# nrflpc.net
KiCad netlist of a schematic drawn in EAGLE
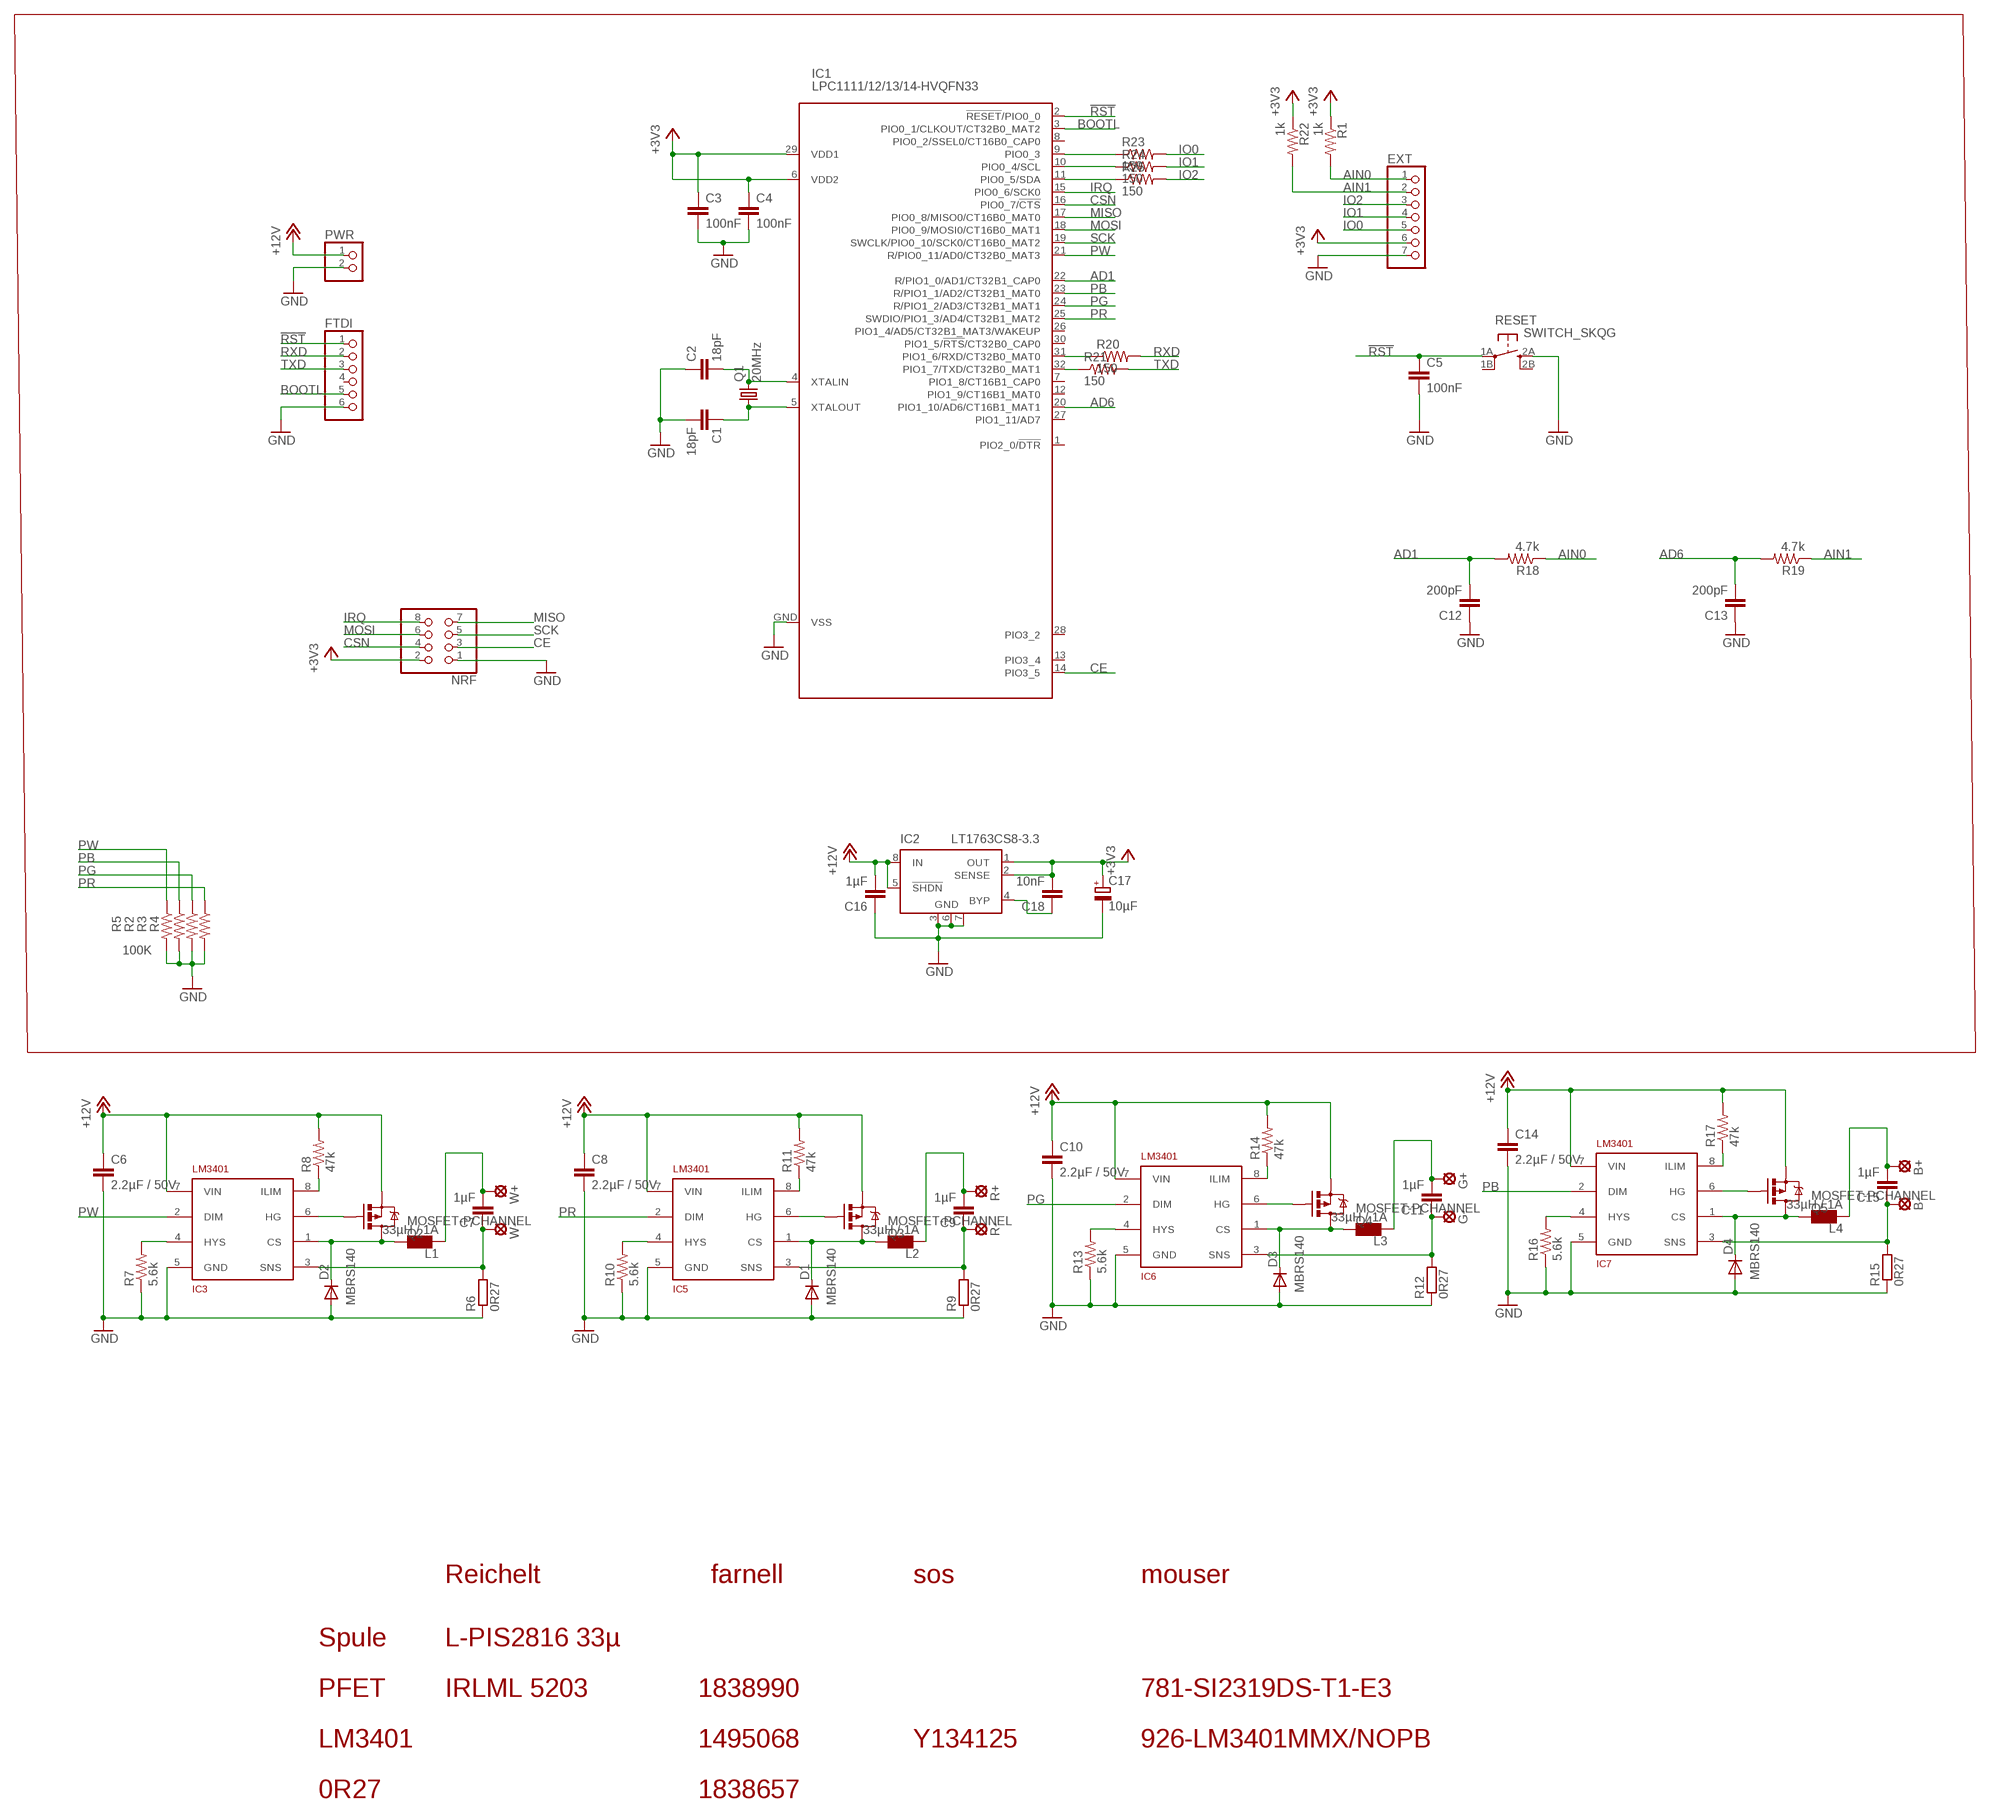
[diagram p0: schematic, sheet 1]

(export (version "E")
  (design (tool "Eeschema 10.0.6"))
  (components
    (comp (ref "B+")
      (value "SE14")
      (footprint "eagle-import:SE14")
      (libsource (lib "eagle-import") (part "SE14"))
    )
    (comp (ref "B-")
      (value "SE14")
      (footprint "eagle-import:SE14")
      (libsource (lib "eagle-import") (part "SE14"))
    )
    (comp (ref "C1")
      (value "18pF")
      (footprint "eagle-import:0402-CAP")
      (libsource (lib "eagle-import") (part "SparkFun-Passives_CAP0402-CAP"))
    )
    (comp (ref "C2")
      (value "18pF")
      (footprint "eagle-import:0402-CAP")
      (libsource (lib "eagle-import") (part "SparkFun-Passives_CAP0402-CAP"))
    )
    (comp (ref "C3")
      (value "100nF")
      (footprint "eagle-import:0402-CAP")
      (libsource (lib "eagle-import") (part "SparkFun-Passives_CAP0402-CAP"))
    )
    (comp (ref "C4")
      (value "100nF")
      (footprint "eagle-import:0402-CAP")
      (libsource (lib "eagle-import") (part "SparkFun-Passives_CAP0402-CAP"))
    )
    (comp (ref "C5")
      (value "100nF")
      (footprint "eagle-import:0402-CAP")
      (libsource (lib "eagle-import") (part "SparkFun-Passives_CAP0402-CAP"))
    )
    (comp (ref "C6")
      (value "2.2µF / 50V")
      (footprint "eagle-import:C1210")
      (libsource (lib "eagle-import") (part "C-EUC1210"))
    )
    (comp (ref "C7")
      (value "1µF")
      (footprint "eagle-import:0805")
      (libsource (lib "eagle-import") (part "CAP0805"))
    )
    (comp (ref "C8")
      (value "2.2µF / 50V")
      (footprint "eagle-import:C1210")
      (libsource (lib "eagle-import") (part "C-EUC1210"))
    )
    (comp (ref "C9")
      (value "1µF")
      (footprint "eagle-import:0805")
      (libsource (lib "eagle-import") (part "CAP0805"))
    )
    (comp (ref "C10")
      (value "2.2µF / 50V")
      (footprint "eagle-import:C1210")
      (libsource (lib "eagle-import") (part "C-EUC1210"))
    )
    (comp (ref "C11")
      (value "1µF")
      (footprint "eagle-import:0805")
      (libsource (lib "eagle-import") (part "CAP0805"))
    )
    (comp (ref "C12")
      (value "200pF")
      (footprint "eagle-import:0402-CAP")
      (libsource (lib "eagle-import") (part "SparkFun-Passives_CAP0402-CAP"))
    )
    (comp (ref "C13")
      (value "200pF")
      (footprint "eagle-import:0402-CAP")
      (libsource (lib "eagle-import") (part "SparkFun-Passives_CAP0402-CAP"))
    )
    (comp (ref "C14")
      (value "2.2µF / 50V")
      (footprint "eagle-import:C1210")
      (libsource (lib "eagle-import") (part "C-EUC1210"))
    )
    (comp (ref "C15")
      (value "1µF")
      (footprint "eagle-import:0805")
      (libsource (lib "eagle-import") (part "CAP0805"))
    )
    (comp (ref "C16")
      (value "1µF")
      (footprint "eagle-import:0805")
      (libsource (lib "eagle-import") (part "CAP0805"))
    )
    (comp (ref "C17")
      (value "10µF")
      (footprint "eagle-import:SMC_A")
      (libsource (lib "eagle-import") (part "CPOL-EUSMCA"))
    )
    (comp (ref "C18")
      (value "10nF")
      (footprint "eagle-import:0402-CAP")
      (libsource (lib "eagle-import") (part "CAP0402-CAP"))
    )
    (comp (ref "D1")
      (value "MBRS140")
      (footprint "eagle-import:SMB")
      (libsource (lib "eagle-import") (part "DIODE-SMB"))
    )
    (comp (ref "D2")
      (value "MBRS140")
      (footprint "eagle-import:SMB")
      (libsource (lib "eagle-import") (part "DIODE-SMB"))
    )
    (comp (ref "D3")
      (value "MBRS140")
      (footprint "eagle-import:SMB")
      (libsource (lib "eagle-import") (part "DIODE-SMB"))
    )
    (comp (ref "D4")
      (value "MBRS140")
      (footprint "eagle-import:SMB")
      (libsource (lib "eagle-import") (part "DIODE-SMB"))
    )
    (comp (ref "EXT")
      (value "PINHD-1X7")
      (footprint "eagle-import:1X07")
      (libsource (lib "eagle-import") (part "PINHD-1X7"))
    )
    (comp (ref "FTDI")
      (value "PINHD-1X6")
      (footprint "eagle-import:1X06")
      (libsource (lib "eagle-import") (part "PINHD-1X6"))
    )
    (comp (ref "G+")
      (value "SE14")
      (footprint "eagle-import:SE14")
      (libsource (lib "eagle-import") (part "SE14"))
    )
    (comp (ref "G-")
      (value "SE14")
      (footprint "eagle-import:SE14")
      (libsource (lib "eagle-import") (part "SE14"))
    )
    (comp (ref "IC1")
      (value "LPC1111/12/13/14-HVQFN33")
      (footprint "eagle-import:HVQFN33")
      (libsource (lib "eagle-import") (part "LPC1111/12/13/14-HVQFN33"))
    )
    (comp (ref "IC2")
      (value "LT1763CS8-3.3")
      (footprint "eagle-import:SOIC8")
      (libsource (lib "eagle-import") (part "LT1763CS8-3.3"))
    )
    (comp (ref "IC3")
      (value "LM3401")
      (footprint "eagle-import:MSOP8")
      (libsource (lib "eagle-import") (part "LM3401"))
    )
    (comp (ref "IC5")
      (value "LM3401")
      (footprint "eagle-import:MSOP8")
      (libsource (lib "eagle-import") (part "LM3401"))
    )
    (comp (ref "IC6")
      (value "LM3401")
      (footprint "eagle-import:MSOP8")
      (libsource (lib "eagle-import") (part "LM3401"))
    )
    (comp (ref "IC7")
      (value "LM3401")
      (footprint "eagle-import:MSOP8")
      (libsource (lib "eagle-import") (part "LM3401"))
    )
    (comp (ref "L1")
      (value "33µH / 1A")
      (footprint "eagle-import:PIS2816")
      (libsource (lib "eagle-import") (part "L_PIS2816"))
    )
    (comp (ref "L2")
      (value "33µH / 1A")
      (footprint "eagle-import:PIS2816")
      (libsource (lib "eagle-import") (part "L_PIS2816"))
    )
    (comp (ref "L3")
      (value "33µH / 1A")
      (footprint "eagle-import:PIS2816")
      (libsource (lib "eagle-import") (part "L_PIS2816"))
    )
    (comp (ref "L4")
      (value "33µH / 1A")
      (footprint "eagle-import:PIS2816")
      (libsource (lib "eagle-import") (part "L_PIS2816"))
    )
    (comp (ref "NRF")
      (value "PINHD-2X4")
      (footprint "eagle-import:2X04")
      (libsource (lib "eagle-import") (part "PINHD-2X4"))
    )
    (comp (ref "PWR")
      (value "PINHD-1X2")
      (footprint "eagle-import:1X02")
      (libsource (lib "eagle-import") (part "PINHD-1X2"))
    )
    (comp (ref "Q1")
      (value "20MHz")
      (footprint "eagle-import:MT")
      (libsource (lib "eagle-import") (part "MT-OSCILLATOR"))
    )
    (comp (ref "Q2")
      (value "MOSFET-PCHANNEL")
      (footprint "eagle-import:SOT23")
      (libsource (lib "eagle-import") (part "MOSFET-PCHANNEL"))
    )
    (comp (ref "Q3")
      (value "MOSFET-PCHANNEL")
      (footprint "eagle-import:SOT23")
      (libsource (lib "eagle-import") (part "MOSFET-PCHANNEL"))
    )
    (comp (ref "Q4")
      (value "MOSFET-PCHANNEL")
      (footprint "eagle-import:SOT23")
      (libsource (lib "eagle-import") (part "MOSFET-PCHANNEL"))
    )
    (comp (ref "Q5")
      (value "MOSFET-PCHANNEL")
      (footprint "eagle-import:SOT23")
      (libsource (lib "eagle-import") (part "MOSFET-PCHANNEL"))
    )
    (comp (ref "R+")
      (value "SE14")
      (footprint "eagle-import:SE14")
      (libsource (lib "eagle-import") (part "SE14"))
    )
    (comp (ref "R-")
      (value "SE14")
      (footprint "eagle-import:SE14")
      (libsource (lib "eagle-import") (part "SE14"))
    )
    (comp (ref "R1")
      (value "1k")
      (footprint "eagle-import:0402-RES")
      (libsource (lib "eagle-import") (part "SparkFun-Resistors_RESISTOR0402-RES"))
    )
    (comp (ref "R2")
      (value "100K")
      (footprint "eagle-import:0402-RES")
      (libsource (lib "eagle-import") (part "SparkFun-Resistors_RESISTOR0402-RES"))
    )
    (comp (ref "R3")
      (value "100K")
      (footprint "eagle-import:0402-RES")
      (libsource (lib "eagle-import") (part "SparkFun-Resistors_RESISTOR0402-RES"))
    )
    (comp (ref "R4")
      (value "100K")
      (footprint "eagle-import:0402-RES")
      (libsource (lib "eagle-import") (part "SparkFun-Resistors_RESISTOR0402-RES"))
    )
    (comp (ref "R5")
      (value "100K")
      (footprint "eagle-import:0402-RES")
      (libsource (lib "eagle-import") (part "SparkFun-Resistors_RESISTOR0402-RES"))
    )
    (comp (ref "R6")
      (value "0R27")
      (footprint "eagle-import:R1206")
      (libsource (lib "eagle-import") (part "R-EU_R1206"))
    )
    (comp (ref "R7")
      (value "5.6k")
      (footprint "eagle-import:0805")
      (libsource (lib "eagle-import") (part "RESISTOR0805-RES"))
    )
    (comp (ref "R8")
      (value "47k")
      (footprint "eagle-import:0805")
      (libsource (lib "eagle-import") (part "RESISTOR0805-RES"))
    )
    (comp (ref "R9")
      (value "0R27")
      (footprint "eagle-import:R1206")
      (libsource (lib "eagle-import") (part "R-EU_R1206"))
    )
    (comp (ref "R10")
      (value "5.6k")
      (footprint "eagle-import:0805")
      (libsource (lib "eagle-import") (part "RESISTOR0805-RES"))
    )
    (comp (ref "R11")
      (value "47k")
      (footprint "eagle-import:0805")
      (libsource (lib "eagle-import") (part "RESISTOR0805-RES"))
    )
    (comp (ref "R12")
      (value "0R27")
      (footprint "eagle-import:R1206")
      (libsource (lib "eagle-import") (part "R-EU_R1206"))
    )
    (comp (ref "R13")
      (value "5.6k")
      (footprint "eagle-import:0805")
      (libsource (lib "eagle-import") (part "RESISTOR0805-RES"))
    )
    (comp (ref "R14")
      (value "47k")
      (footprint "eagle-import:0805")
      (libsource (lib "eagle-import") (part "RESISTOR0805-RES"))
    )
    (comp (ref "R15")
      (value "0R27")
      (footprint "eagle-import:R1206")
      (libsource (lib "eagle-import") (part "R-EU_R1206"))
    )
    (comp (ref "R16")
      (value "5.6k")
      (footprint "eagle-import:0805")
      (libsource (lib "eagle-import") (part "RESISTOR0805-RES"))
    )
    (comp (ref "R17")
      (value "47k")
      (footprint "eagle-import:0805")
      (libsource (lib "eagle-import") (part "RESISTOR0805-RES"))
    )
    (comp (ref "R18")
      (value "4.7k")
      (footprint "eagle-import:0402-RES")
      (libsource (lib "eagle-import") (part "SparkFun-Resistors_RESISTOR0402-RES"))
    )
    (comp (ref "R19")
      (value "4.7k")
      (footprint "eagle-import:0402-RES")
      (libsource (lib "eagle-import") (part "SparkFun-Resistors_RESISTOR0402-RES"))
    )
    (comp (ref "R20")
      (value "150")
      (footprint "eagle-import:0402-RES")
      (libsource (lib "eagle-import") (part "SparkFun-Resistors_RESISTOR0402-RES"))
    )
    (comp (ref "R21")
      (value "150")
      (footprint "eagle-import:0402-RES")
      (libsource (lib "eagle-import") (part "SparkFun-Resistors_RESISTOR0402-RES"))
    )
    (comp (ref "R22")
      (value "1k")
      (footprint "eagle-import:0402-RES")
      (libsource (lib "eagle-import") (part "SparkFun-Resistors_RESISTOR0402-RES"))
    )
    (comp (ref "R23")
      (value "150")
      (footprint "eagle-import:0402-RES")
      (libsource (lib "eagle-import") (part "SparkFun-Resistors_RESISTOR0402-RES"))
    )
    (comp (ref "R24")
      (value "150")
      (footprint "eagle-import:0402-RES")
      (libsource (lib "eagle-import") (part "SparkFun-Resistors_RESISTOR0402-RES"))
    )
    (comp (ref "R25")
      (value "150")
      (footprint "eagle-import:0402-RES")
      (libsource (lib "eagle-import") (part "SparkFun-Resistors_RESISTOR0402-RES"))
    )
    (comp (ref "RESET")
      (value "SWITCH_SKQG")
      (footprint "eagle-import:SWITCH_SKQG")
      (libsource (lib "eagle-import") (part "SWITCH_SKQG"))
    )
    (comp (ref "W+")
      (value "SE14")
      (footprint "eagle-import:SE14")
      (libsource (lib "eagle-import") (part "SE14"))
    )
    (comp (ref "W-")
      (value "SE14")
      (footprint "eagle-import:SE14")
      (libsource (lib "eagle-import") (part "SE14"))
    )
  )
  (nets
    (net (code "1") (name "+3V3") (class "Default")
      (node (ref "C17") (pin "+") (pinfunction "+_+") (pintype "passive"))
      (node (ref "C18") (pin "2") (pinfunction "2_2") (pintype "passive"))
      (node (ref "C3") (pin "1") (pinfunction "1_1") (pintype "passive"))
      (node (ref "C4") (pin "1") (pinfunction "1_1") (pintype "passive"))
      (node (ref "EXT") (pin "6") (pinfunction "6_6") (pintype "passive"))
      (node (ref "IC1") (pin "29") (pinfunction "VDD1_29") (pintype "power_in"))
      (node (ref "IC1") (pin "6") (pinfunction "VDD2_6") (pintype "power_in"))
      (node (ref "IC2") (pin "1") (pinfunction "OUT_1") (pintype "passive"))
      (node (ref "IC2") (pin "2") (pinfunction "SENSE_2") (pintype "input"))
      (node (ref "NRF") (pin "2") (pinfunction "2_2") (pintype "passive"))
      (node (ref "R1") (pin "1") (pinfunction "1_1") (pintype "passive"))
      (node (ref "R22") (pin "1") (pinfunction "1_1") (pintype "passive"))
    )
    (net (code "2") (name "+12V") (class "Default")
      (node (ref "C10") (pin "1") (pinfunction "1_1") (pintype "passive"))
      (node (ref "C14") (pin "1") (pinfunction "1_1") (pintype "passive"))
      (node (ref "C16") (pin "2") (pinfunction "2_2") (pintype "passive"))
      (node (ref "C6") (pin "1") (pinfunction "1_1") (pintype "passive"))
      (node (ref "C8") (pin "1") (pinfunction "1_1") (pintype "passive"))
      (node (ref "IC2") (pin "5") (pinfunction "~{SHDN}_5") (pintype "input"))
      (node (ref "IC2") (pin "8") (pinfunction "IN_8") (pintype "input"))
      (node (ref "IC3") (pin "7") (pinfunction "VIN_7") (pintype "bidirectional"))
      (node (ref "IC5") (pin "7") (pinfunction "VIN_7") (pintype "bidirectional"))
      (node (ref "IC6") (pin "7") (pinfunction "VIN_7") (pintype "bidirectional"))
      (node (ref "IC7") (pin "7") (pinfunction "VIN_7") (pintype "bidirectional"))
      (node (ref "PWR") (pin "1") (pinfunction "1_1") (pintype "passive"))
      (node (ref "Q2") (pin "2") (pinfunction "S_2") (pintype "passive"))
      (node (ref "Q3") (pin "2") (pinfunction "S_2") (pintype "passive"))
      (node (ref "Q4") (pin "2") (pinfunction "S_2") (pintype "passive"))
      (node (ref "Q5") (pin "2") (pinfunction "S_2") (pintype "passive"))
      (node (ref "R11") (pin "2") (pinfunction "2_2") (pintype "passive"))
      (node (ref "R14") (pin "2") (pinfunction "2_2") (pintype "passive"))
      (node (ref "R17") (pin "2") (pinfunction "2_2") (pintype "passive"))
      (node (ref "R8") (pin "2") (pinfunction "2_2") (pintype "passive"))
    )
    (net (code "3") (name "/AD1") (class "Default")
      (node (ref "C12") (pin "2") (pinfunction "2_2") (pintype "passive"))
      (node (ref "IC1") (pin "22") (pinfunction "R/PIO1_0/AD1/CT32B1_CAP0_22") (pintype "bidirectional"))
      (node (ref "R18") (pin "2") (pinfunction "2_2") (pintype "passive"))
    )
    (net (code "4") (name "/AD6") (class "Default")
      (node (ref "C13") (pin "2") (pinfunction "2_2") (pintype "passive"))
      (node (ref "IC1") (pin "20") (pinfunction "PIO1_10/AD6/CT16B1_MAT1_20") (pintype "bidirectional"))
      (node (ref "R19") (pin "2") (pinfunction "2_2") (pintype "passive"))
    )
    (net (code "5") (name "/AIN0") (class "Default")
      (node (ref "EXT") (pin "1") (pinfunction "1_1") (pintype "passive"))
      (node (ref "R1") (pin "2") (pinfunction "2_2") (pintype "passive"))
      (node (ref "R18") (pin "1") (pinfunction "1_1") (pintype "passive"))
    )
    (net (code "6") (name "/AIN1") (class "Default")
      (node (ref "EXT") (pin "2") (pinfunction "2_2") (pintype "passive"))
      (node (ref "R19") (pin "1") (pinfunction "1_1") (pintype "passive"))
      (node (ref "R22") (pin "2") (pinfunction "2_2") (pintype "passive"))
    )
    (net (code "7") (name "/BOOTL") (class "Default")
      (node (ref "FTDI") (pin "5") (pinfunction "5_5") (pintype "passive"))
      (node (ref "IC1") (pin "3") (pinfunction "PIO0_1/CLKOUT/CT32B0_MAT2_3") (pintype "bidirectional"))
    )
    (net (code "8") (name "/CE") (class "Default")
      (node (ref "IC1") (pin "14") (pinfunction "PIO3_5_14") (pintype "bidirectional"))
      (node (ref "NRF") (pin "3") (pinfunction "3_3") (pintype "passive"))
    )
    (net (code "9") (name "/CSN") (class "Default")
      (node (ref "IC1") (pin "16") (pinfunction "PIO0_7/~{CTS}_16") (pintype "bidirectional"))
      (node (ref "NRF") (pin "4") (pinfunction "4_4") (pintype "passive"))
    )
    (net (code "10") (name "/IO0") (class "Default")
      (node (ref "EXT") (pin "5") (pinfunction "5_5") (pintype "passive"))
      (node (ref "R23") (pin "2") (pinfunction "2_2") (pintype "passive"))
    )
    (net (code "11") (name "/IO1") (class "Default")
      (node (ref "EXT") (pin "4") (pinfunction "4_4") (pintype "passive"))
      (node (ref "R24") (pin "2") (pinfunction "2_2") (pintype "passive"))
    )
    (net (code "12") (name "/IO2") (class "Default")
      (node (ref "EXT") (pin "3") (pinfunction "3_3") (pintype "passive"))
      (node (ref "R25") (pin "2") (pinfunction "2_2") (pintype "passive"))
    )
    (net (code "13") (name "/IRQ") (class "Default")
      (node (ref "IC1") (pin "15") (pinfunction "PIO0_6/SCK0_15") (pintype "bidirectional"))
      (node (ref "NRF") (pin "8") (pinfunction "8_8") (pintype "passive"))
    )
    (net (code "14") (name "/MISO") (class "Default")
      (node (ref "IC1") (pin "17") (pinfunction "PIO0_8/MISO0/CT16B0_MAT0_17") (pintype "bidirectional"))
      (node (ref "NRF") (pin "7") (pinfunction "7_7") (pintype "passive"))
    )
    (net (code "15") (name "/MOSI") (class "Default")
      (node (ref "IC1") (pin "18") (pinfunction "PIO0_9/MOSI0/CT16B0_MAT1_18") (pintype "bidirectional"))
      (node (ref "NRF") (pin "6") (pinfunction "6_6") (pintype "passive"))
    )
    (net (code "16") (name "/PB") (class "Default")
      (node (ref "IC1") (pin "23") (pinfunction "R/PIO1_1/AD2/CT32B1_MAT0_23") (pintype "bidirectional"))
      (node (ref "IC7") (pin "2") (pinfunction "DIM_2") (pintype "bidirectional"))
      (node (ref "R2") (pin "1") (pinfunction "1_1") (pintype "passive"))
    )
    (net (code "17") (name "/PG") (class "Default")
      (node (ref "IC1") (pin "24") (pinfunction "R/PIO1_2/AD3/CT32B1_MAT1_24") (pintype "bidirectional"))
      (node (ref "IC6") (pin "2") (pinfunction "DIM_2") (pintype "bidirectional"))
      (node (ref "R3") (pin "1") (pinfunction "1_1") (pintype "passive"))
    )
    (net (code "18") (name "/PR") (class "Default")
      (node (ref "IC1") (pin "25") (pinfunction "SWDIO/PIO1_3/AD4/CT32B1_MAT2_25") (pintype "bidirectional"))
      (node (ref "IC5") (pin "2") (pinfunction "DIM_2") (pintype "bidirectional"))
      (node (ref "R4") (pin "1") (pinfunction "1_1") (pintype "passive"))
    )
    (net (code "19") (name "/PW") (class "Default")
      (node (ref "IC1") (pin "21") (pinfunction "R/PIO0_11/AD0/CT32B0_MAT3_21") (pintype "bidirectional"))
      (node (ref "IC3") (pin "2") (pinfunction "DIM_2") (pintype "bidirectional"))
      (node (ref "R5") (pin "1") (pinfunction "1_1") (pintype "passive"))
    )
    (net (code "20") (name "/RXD") (class "Default")
      (node (ref "FTDI") (pin "2") (pinfunction "2_2") (pintype "passive"))
      (node (ref "R20") (pin "2") (pinfunction "2_2") (pintype "passive"))
    )
    (net (code "21") (name "/SCK") (class "Default")
      (node (ref "IC1") (pin "19") (pinfunction "SWCLK/PIO0_10/SCK0/CT16B0_MAT2_19") (pintype "bidirectional"))
      (node (ref "NRF") (pin "5") (pinfunction "5_5") (pintype "passive"))
    )
    (net (code "22") (name "/TXD") (class "Default")
      (node (ref "FTDI") (pin "3") (pinfunction "3_3") (pintype "passive"))
      (node (ref "R21") (pin "2") (pinfunction "2_2") (pintype "passive"))
    )
    (net (code "23") (name "/~{RST}") (class "Default")
      (node (ref "C5") (pin "1") (pinfunction "1_1") (pintype "passive"))
      (node (ref "FTDI") (pin "1") (pinfunction "1_1") (pintype "passive"))
      (node (ref "IC1") (pin "2") (pinfunction "~{RESET}/PIO0_0_2") (pintype "bidirectional"))
      (node (ref "RESET") (pin "1A") (pinfunction "1A_1A") (pintype "passive"))
    )
    (net (code "24") (name "GND") (class "Default")
      (node (ref "C1") (pin "2") (pinfunction "2_2") (pintype "passive"))
      (node (ref "C10") (pin "2") (pinfunction "2_2") (pintype "passive"))
      (node (ref "C12") (pin "1") (pinfunction "1_1") (pintype "passive"))
      (node (ref "C13") (pin "1") (pinfunction "1_1") (pintype "passive"))
      (node (ref "C14") (pin "2") (pinfunction "2_2") (pintype "passive"))
      (node (ref "C16") (pin "1") (pinfunction "1_1") (pintype "passive"))
      (node (ref "C17") (pin "-") (pinfunction "-_-") (pintype "passive"))
      (node (ref "C2") (pin "1") (pinfunction "1_1") (pintype "passive"))
      (node (ref "C3") (pin "2") (pinfunction "2_2") (pintype "passive"))
      (node (ref "C4") (pin "2") (pinfunction "2_2") (pintype "passive"))
      (node (ref "C5") (pin "2") (pinfunction "2_2") (pintype "passive"))
      (node (ref "C6") (pin "2") (pinfunction "2_2") (pintype "passive"))
      (node (ref "C8") (pin "2") (pinfunction "2_2") (pintype "passive"))
      (node (ref "D1") (pin "A") (pinfunction "A_A") (pintype "passive"))
      (node (ref "D2") (pin "A") (pinfunction "A_A") (pintype "passive"))
      (node (ref "D3") (pin "A") (pinfunction "A_A") (pintype "passive"))
      (node (ref "D4") (pin "A") (pinfunction "A_A") (pintype "passive"))
      (node (ref "EXT") (pin "7") (pinfunction "7_7") (pintype "passive"))
      (node (ref "FTDI") (pin "6") (pinfunction "6_6") (pintype "passive"))
      (node (ref "IC1") (pin "GND") (pinfunction "VSS_GND") (pintype "power_in"))
      (node (ref "IC2") (pin "3") (pinfunction "GND_3") (pintype "power_in"))
      (node (ref "IC2") (pin "6") (pinfunction "GND_6") (pintype "power_in"))
      (node (ref "IC2") (pin "7") (pinfunction "GND_7") (pintype "power_in"))
      (node (ref "IC3") (pin "5") (pinfunction "GND_5") (pintype "bidirectional"))
      (node (ref "IC5") (pin "5") (pinfunction "GND_5") (pintype "bidirectional"))
      (node (ref "IC6") (pin "5") (pinfunction "GND_5") (pintype "bidirectional"))
      (node (ref "IC7") (pin "5") (pinfunction "GND_5") (pintype "bidirectional"))
      (node (ref "NRF") (pin "1") (pinfunction "1_1") (pintype "passive"))
      (node (ref "PWR") (pin "2") (pinfunction "2_2") (pintype "passive"))
      (node (ref "R10") (pin "1") (pinfunction "1_1") (pintype "passive"))
      (node (ref "R12") (pin "1") (pinfunction "1_1") (pintype "passive"))
      (node (ref "R13") (pin "1") (pinfunction "1_1") (pintype "passive"))
      (node (ref "R15") (pin "1") (pinfunction "1_1") (pintype "passive"))
      (node (ref "R16") (pin "1") (pinfunction "1_1") (pintype "passive"))
      (node (ref "R2") (pin "2") (pinfunction "2_2") (pintype "passive"))
      (node (ref "R3") (pin "2") (pinfunction "2_2") (pintype "passive"))
      (node (ref "R4") (pin "2") (pinfunction "2_2") (pintype "passive"))
      (node (ref "R5") (pin "2") (pinfunction "2_2") (pintype "passive"))
      (node (ref "R6") (pin "1") (pinfunction "1_1") (pintype "passive"))
      (node (ref "R7") (pin "1") (pinfunction "1_1") (pintype "passive"))
      (node (ref "R9") (pin "1") (pinfunction "1_1") (pintype "passive"))
      (node (ref "RESET") (pin "2A") (pinfunction "2A_2A") (pintype "passive"))
    )
    (net (code "25") (name "Net-(IC1-PIO0_3)") (class "Default")
      (node (ref "IC1") (pin "9") (pinfunction "PIO0_3_9") (pintype "bidirectional"))
      (node (ref "R23") (pin "1") (pinfunction "1_1") (pintype "passive"))
    )
    (net (code "26") (name "Net-(IC1-PIO0_4{slash}SCL)") (class "Default")
      (node (ref "IC1") (pin "10") (pinfunction "PIO0_4/SCL_10") (pintype "bidirectional"))
      (node (ref "R24") (pin "1") (pinfunction "1_1") (pintype "passive"))
    )
    (net (code "27") (name "Net-(IC1-PIO0_5{slash}SDA)") (class "Default")
      (node (ref "IC1") (pin "11") (pinfunction "PIO0_5/SDA_11") (pintype "bidirectional"))
      (node (ref "R25") (pin "1") (pinfunction "1_1") (pintype "passive"))
    )
    (net (code "28") (name "Net-(IC1-PIO1_6{slash}RXD{slash}CT32B0_MAT0)") (class "Default")
      (node (ref "IC1") (pin "31") (pinfunction "PIO1_6/RXD/CT32B0_MAT0_31") (pintype "bidirectional"))
      (node (ref "R20") (pin "1") (pinfunction "1_1") (pintype "passive"))
    )
    (net (code "29") (name "Net-(IC1-PIO1_7{slash}TXD{slash}CT32B0_MAT1)") (class "Default")
      (node (ref "IC1") (pin "32") (pinfunction "PIO1_7/TXD/CT32B0_MAT1_32") (pintype "bidirectional"))
      (node (ref "R21") (pin "1") (pinfunction "1_1") (pintype "passive"))
    )
    (net (code "30") (name "Net-(IC1-XTALIN)") (class "Default")
      (node (ref "C2") (pin "2") (pinfunction "2_2") (pintype "passive"))
      (node (ref "IC1") (pin "4") (pinfunction "XTALIN_4") (pintype "passive"))
      (node (ref "Q1") (pin "3") (pinfunction "2_3") (pintype "passive"))
    )
    (net (code "31") (name "Net-(IC1-XTALOUT)") (class "Default")
      (node (ref "C1") (pin "1") (pinfunction "1_1") (pintype "passive"))
      (node (ref "IC1") (pin "5") (pinfunction "XTALOUT_5") (pintype "passive"))
      (node (ref "Q1") (pin "1") (pinfunction "1_1") (pintype "passive"))
    )
    (net (code "32") (name "Net-(IC2-BYP)") (class "Default")
      (node (ref "C18") (pin "1") (pinfunction "1_1") (pintype "passive"))
      (node (ref "IC2") (pin "4") (pinfunction "BYP_4") (pintype "input"))
    )
    (net (code "33") (name "Net-(IC3-CS)") (class "Default")
      (node (ref "D2") (pin "C") (pinfunction "C_C") (pintype "passive"))
      (node (ref "IC3") (pin "1") (pinfunction "CS_1") (pintype "bidirectional"))
      (node (ref "L1") (pin "P$1") (pinfunction "1_P$1") (pintype "passive"))
      (node (ref "Q2") (pin "3") (pinfunction "D_3") (pintype "passive"))
    )
    (net (code "34") (name "Net-(IC3-HG)") (class "Default")
      (node (ref "IC3") (pin "6") (pinfunction "HG_6") (pintype "bidirectional"))
      (node (ref "Q2") (pin "1") (pinfunction "G_1") (pintype "passive"))
    )
    (net (code "35") (name "Net-(IC3-HYS)") (class "Default")
      (node (ref "IC3") (pin "4") (pinfunction "HYS_4") (pintype "bidirectional"))
      (node (ref "R7") (pin "2") (pinfunction "2_2") (pintype "passive"))
    )
    (net (code "36") (name "Net-(IC3-ILIM)") (class "Default")
      (node (ref "IC3") (pin "8") (pinfunction "ILIM_8") (pintype "bidirectional"))
      (node (ref "R8") (pin "1") (pinfunction "1_1") (pintype "passive"))
    )
    (net (code "37") (name "Net-(IC3-SNS)") (class "Default")
      (node (ref "C7") (pin "1") (pinfunction "1_1") (pintype "passive"))
      (node (ref "IC3") (pin "3") (pinfunction "SNS_3") (pintype "bidirectional"))
      (node (ref "R6") (pin "2") (pinfunction "2_2") (pintype "passive"))
      (node (ref "W-") (pin "MP") (pinfunction "MP_MP") (pintype "passive"))
    )
    (net (code "38") (name "Net-(IC5-CS)") (class "Default")
      (node (ref "D1") (pin "C") (pinfunction "C_C") (pintype "passive"))
      (node (ref "IC5") (pin "1") (pinfunction "CS_1") (pintype "bidirectional"))
      (node (ref "L2") (pin "P$1") (pinfunction "1_P$1") (pintype "passive"))
      (node (ref "Q3") (pin "3") (pinfunction "D_3") (pintype "passive"))
    )
    (net (code "39") (name "Net-(IC5-HG)") (class "Default")
      (node (ref "IC5") (pin "6") (pinfunction "HG_6") (pintype "bidirectional"))
      (node (ref "Q3") (pin "1") (pinfunction "G_1") (pintype "passive"))
    )
    (net (code "40") (name "Net-(IC5-HYS)") (class "Default")
      (node (ref "IC5") (pin "4") (pinfunction "HYS_4") (pintype "bidirectional"))
      (node (ref "R10") (pin "2") (pinfunction "2_2") (pintype "passive"))
    )
    (net (code "41") (name "Net-(IC5-ILIM)") (class "Default")
      (node (ref "IC5") (pin "8") (pinfunction "ILIM_8") (pintype "bidirectional"))
      (node (ref "R11") (pin "1") (pinfunction "1_1") (pintype "passive"))
    )
    (net (code "42") (name "Net-(IC5-SNS)") (class "Default")
      (node (ref "C9") (pin "1") (pinfunction "1_1") (pintype "passive"))
      (node (ref "IC5") (pin "3") (pinfunction "SNS_3") (pintype "bidirectional"))
      (node (ref "R-") (pin "MP") (pinfunction "MP_MP") (pintype "passive"))
      (node (ref "R9") (pin "2") (pinfunction "2_2") (pintype "passive"))
    )
    (net (code "43") (name "Net-(IC6-CS)") (class "Default")
      (node (ref "D3") (pin "C") (pinfunction "C_C") (pintype "passive"))
      (node (ref "IC6") (pin "1") (pinfunction "CS_1") (pintype "bidirectional"))
      (node (ref "L3") (pin "P$1") (pinfunction "1_P$1") (pintype "passive"))
      (node (ref "Q4") (pin "3") (pinfunction "D_3") (pintype "passive"))
    )
    (net (code "44") (name "Net-(IC6-HG)") (class "Default")
      (node (ref "IC6") (pin "6") (pinfunction "HG_6") (pintype "bidirectional"))
      (node (ref "Q4") (pin "1") (pinfunction "G_1") (pintype "passive"))
    )
    (net (code "45") (name "Net-(IC6-HYS)") (class "Default")
      (node (ref "IC6") (pin "4") (pinfunction "HYS_4") (pintype "bidirectional"))
      (node (ref "R13") (pin "2") (pinfunction "2_2") (pintype "passive"))
    )
    (net (code "46") (name "Net-(IC6-ILIM)") (class "Default")
      (node (ref "IC6") (pin "8") (pinfunction "ILIM_8") (pintype "bidirectional"))
      (node (ref "R14") (pin "1") (pinfunction "1_1") (pintype "passive"))
    )
    (net (code "47") (name "Net-(IC6-SNS)") (class "Default")
      (node (ref "C11") (pin "1") (pinfunction "1_1") (pintype "passive"))
      (node (ref "G-") (pin "MP") (pinfunction "MP_MP") (pintype "passive"))
      (node (ref "IC6") (pin "3") (pinfunction "SNS_3") (pintype "bidirectional"))
      (node (ref "R12") (pin "2") (pinfunction "2_2") (pintype "passive"))
    )
    (net (code "48") (name "Net-(IC7-CS)") (class "Default")
      (node (ref "D4") (pin "C") (pinfunction "C_C") (pintype "passive"))
      (node (ref "IC7") (pin "1") (pinfunction "CS_1") (pintype "bidirectional"))
      (node (ref "L4") (pin "P$1") (pinfunction "1_P$1") (pintype "passive"))
      (node (ref "Q5") (pin "3") (pinfunction "D_3") (pintype "passive"))
    )
    (net (code "49") (name "Net-(IC7-HG)") (class "Default")
      (node (ref "IC7") (pin "6") (pinfunction "HG_6") (pintype "bidirectional"))
      (node (ref "Q5") (pin "1") (pinfunction "G_1") (pintype "passive"))
    )
    (net (code "50") (name "Net-(IC7-HYS)") (class "Default")
      (node (ref "IC7") (pin "4") (pinfunction "HYS_4") (pintype "bidirectional"))
      (node (ref "R16") (pin "2") (pinfunction "2_2") (pintype "passive"))
    )
    (net (code "51") (name "Net-(IC7-ILIM)") (class "Default")
      (node (ref "IC7") (pin "8") (pinfunction "ILIM_8") (pintype "bidirectional"))
      (node (ref "R17") (pin "1") (pinfunction "1_1") (pintype "passive"))
    )
    (net (code "52") (name "Net-(IC7-SNS)") (class "Default")
      (node (ref "B-") (pin "MP") (pinfunction "MP_MP") (pintype "passive"))
      (node (ref "C15") (pin "1") (pinfunction "1_1") (pintype "passive"))
      (node (ref "IC7") (pin "3") (pinfunction "SNS_3") (pintype "bidirectional"))
      (node (ref "R15") (pin "2") (pinfunction "2_2") (pintype "passive"))
    )
    (net (code "53") (name "Net-(L1-2)") (class "Default")
      (node (ref "C7") (pin "2") (pinfunction "2_2") (pintype "passive"))
      (node (ref "L1") (pin "P$2") (pinfunction "2_P$2") (pintype "passive"))
      (node (ref "W+") (pin "MP") (pinfunction "MP_MP") (pintype "passive"))
    )
    (net (code "54") (name "Net-(L2-2)") (class "Default")
      (node (ref "C9") (pin "2") (pinfunction "2_2") (pintype "passive"))
      (node (ref "L2") (pin "P$2") (pinfunction "2_P$2") (pintype "passive"))
      (node (ref "R+") (pin "MP") (pinfunction "MP_MP") (pintype "passive"))
    )
    (net (code "55") (name "Net-(L3-2)") (class "Default")
      (node (ref "C11") (pin "2") (pinfunction "2_2") (pintype "passive"))
      (node (ref "G+") (pin "MP") (pinfunction "MP_MP") (pintype "passive"))
      (node (ref "L3") (pin "P$2") (pinfunction "2_P$2") (pintype "passive"))
    )
    (net (code "56") (name "Net-(L4-2)") (class "Default")
      (node (ref "B+") (pin "MP") (pinfunction "MP_MP") (pintype "passive"))
      (node (ref "C15") (pin "2") (pinfunction "2_2") (pintype "passive"))
      (node (ref "L4") (pin "P$2") (pinfunction "2_P$2") (pintype "passive"))
    )
    (net (code "57") (name "unconnected-(FTDI-Pad4)") (class "Default")
      (node (ref "FTDI") (pin "4") (pinfunction "4_4") (pintype "passive"))
    )
    (net (code "58") (name "unconnected-(IC1-PIO0_2{slash}SSEL0{slash}CT16B0_CAP0-Pad8)") (class "Default")
      (node (ref "IC1") (pin "8") (pinfunction "PIO0_2/SSEL0/CT16B0_CAP0_8") (pintype "bidirectional"))
    )
    (net (code "59") (name "unconnected-(IC1-PIO1_4{slash}AD5{slash}CT32B1_MAT3{slash}WAKEUP-Pad26)") (class "Default")
      (node (ref "IC1") (pin "26") (pinfunction "PIO1_4/AD5/CT32B1_MAT3/WAKEUP_26") (pintype "bidirectional"))
    )
    (net (code "60") (name "unconnected-(IC1-PIO1_5{slash}~{RTS}{slash}CT32B0_CAP0-Pad30)") (class "Default")
      (node (ref "IC1") (pin "30") (pinfunction "PIO1_5/~{RTS}/CT32B0_CAP0_30") (pintype "bidirectional"))
    )
    (net (code "61") (name "unconnected-(IC1-PIO1_8{slash}CT16B1_CAP0-Pad7)") (class "Default")
      (node (ref "IC1") (pin "7") (pinfunction "PIO1_8/CT16B1_CAP0_7") (pintype "bidirectional"))
    )
    (net (code "62") (name "unconnected-(IC1-PIO1_9{slash}CT16B1_MAT0-Pad12)") (class "Default")
      (node (ref "IC1") (pin "12") (pinfunction "PIO1_9/CT16B1_MAT0_12") (pintype "bidirectional"))
    )
    (net (code "63") (name "unconnected-(IC1-PIO1_11{slash}AD7-Pad27)") (class "Default")
      (node (ref "IC1") (pin "27") (pinfunction "PIO1_11/AD7_27") (pintype "bidirectional"))
    )
    (net (code "64") (name "unconnected-(IC1-PIO2_0{slash}~{DTR}-Pad1)") (class "Default")
      (node (ref "IC1") (pin "1") (pinfunction "PIO2_0/~{DTR}_1") (pintype "bidirectional"))
    )
    (net (code "65") (name "unconnected-(IC1-PIO3_2-Pad28)") (class "Default")
      (node (ref "IC1") (pin "28") (pinfunction "PIO3_2_28") (pintype "bidirectional"))
    )
    (net (code "66") (name "unconnected-(IC1-PIO3_4-Pad13)") (class "Default")
      (node (ref "IC1") (pin "13") (pinfunction "PIO3_4_13") (pintype "bidirectional"))
    )
    (net (code "67") (name "unconnected-(RESET-Pad1B)") (class "Default")
      (node (ref "RESET") (pin "1B") (pinfunction "1B_1B") (pintype "passive"))
    )
    (net (code "68") (name "unconnected-(RESET-Pad2B)") (class "Default")
      (node (ref "RESET") (pin "2B") (pinfunction "2B_2B") (pintype "passive"))
    )
  )
)
